# Inductive_measurement.net
KiCad netlist of a schematic drawn in Altium Designer
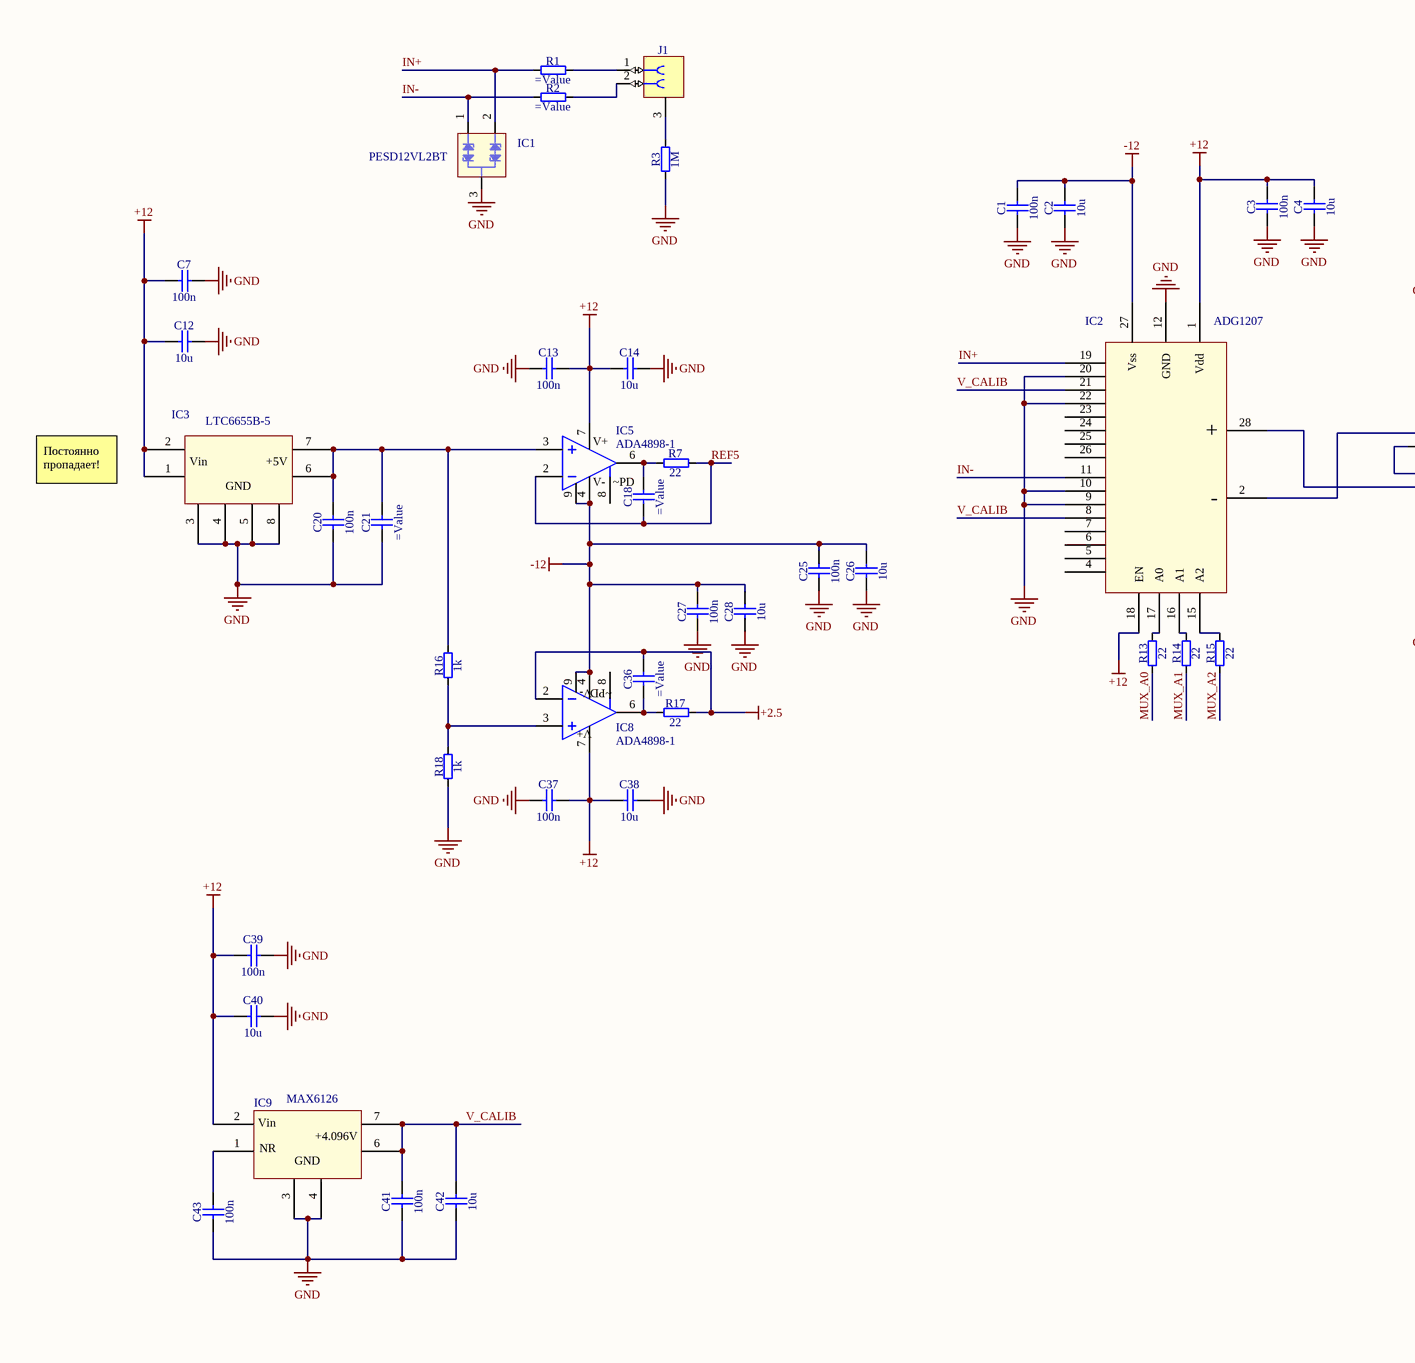
[diagram p0: Inductive_measurement.SchDoc, left]
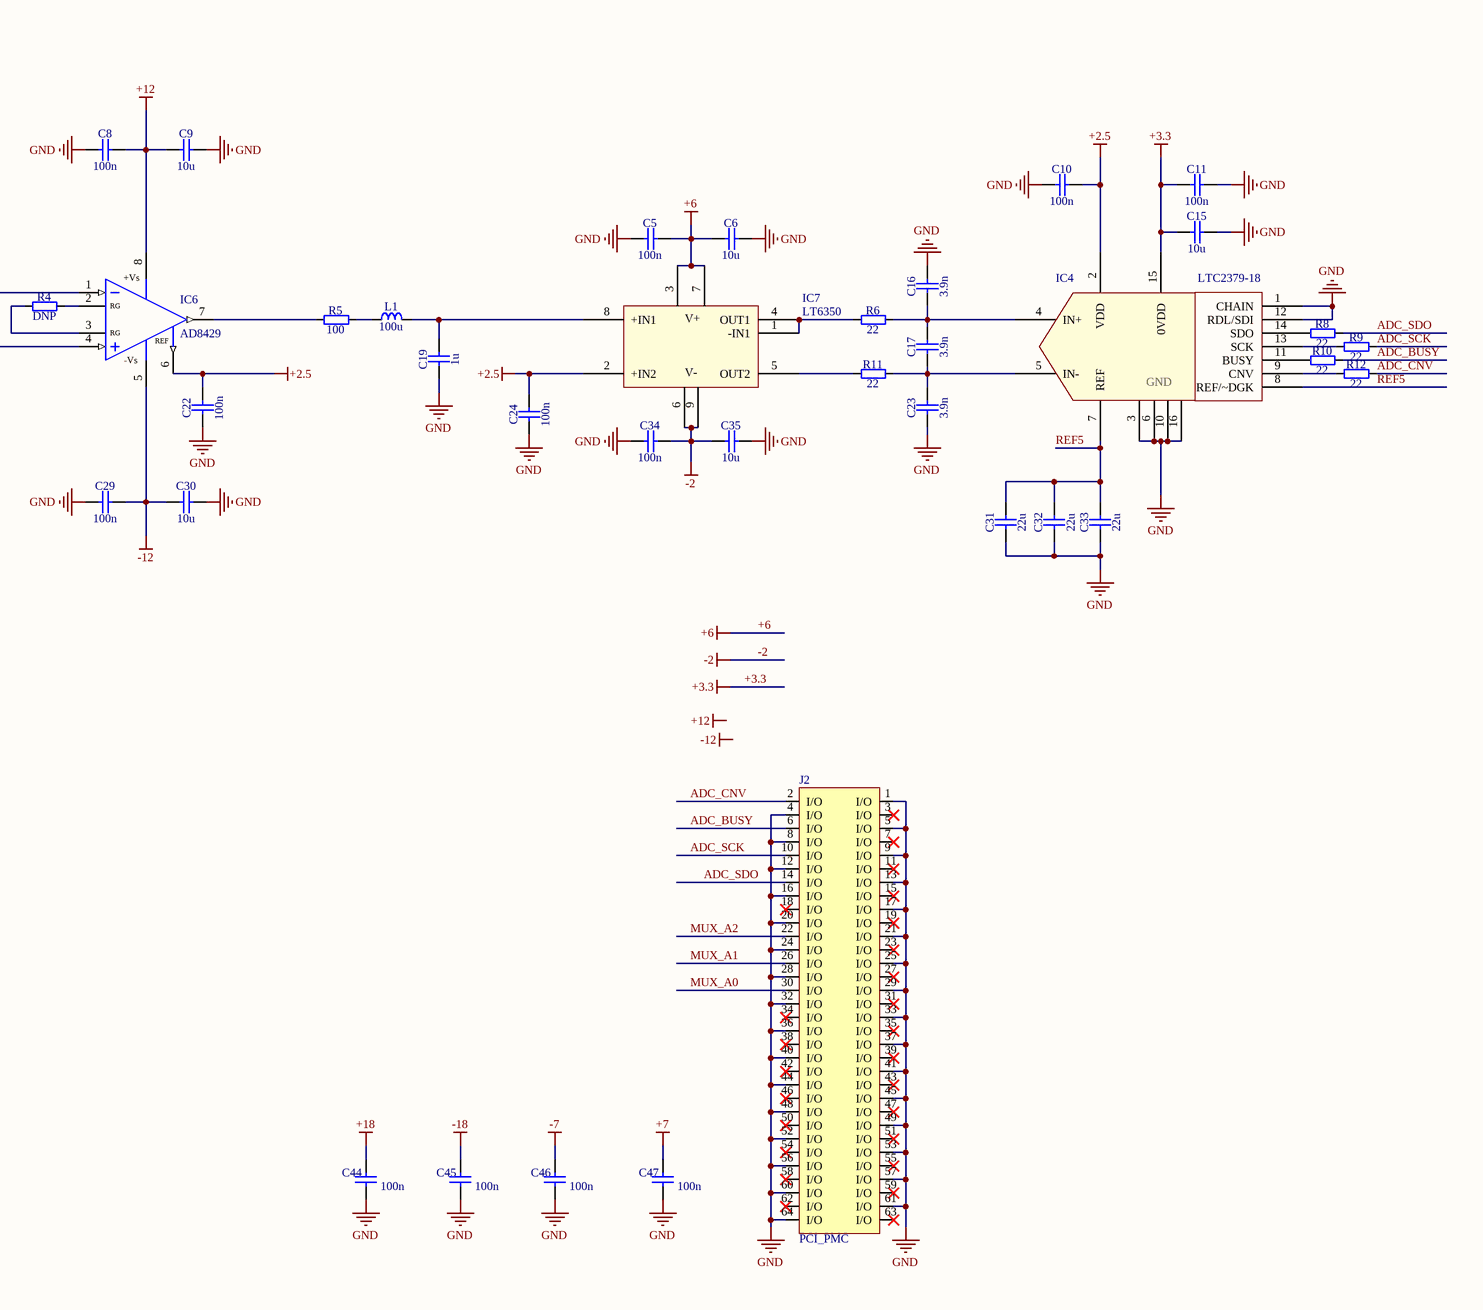
[diagram p1: Inductive_measurement.SchDoc, right]

(export (version "E")
  (design (tool "Eeschema 10.0.6"))
  (components
    (comp (ref "C1") (value "100n") (footprint "0603") (libsource (lib "intS") (part "Capacitor")))
    (comp (ref "C2") (value "10u") (footprint "0603") (libsource (lib "intS") (part "Capacitor")))
    (comp (ref "C3") (value "100n") (footprint "0603") (libsource (lib "intS") (part "Capacitor")))
    (comp (ref "C4") (value "10u") (footprint "0603") (libsource (lib "intS") (part "Capacitor")))
    (comp (ref "C5") (value "100n") (footprint "0603") (libsource (lib "intS") (part "Capacitor")))
    (comp (ref "C6") (value "10u") (footprint "0603") (libsource (lib "intS") (part "Capacitor")))
    (comp (ref "C7") (value "100n") (footprint "0603") (libsource (lib "intS") (part "Capacitor")))
    (comp (ref "C8") (value "100n") (footprint "0603") (libsource (lib "intS") (part "Capacitor")))
    (comp (ref "C9") (value "10u") (footprint "0603") (libsource (lib "intS") (part "Capacitor")))
    (comp (ref "C10") (value "100n") (footprint "0603") (libsource (lib "intS") (part "Capacitor")))
    (comp (ref "C11") (value "100n") (footprint "0603") (libsource (lib "intS") (part "Capacitor")))
    (comp (ref "C12") (value "10u") (footprint "0603") (libsource (lib "intS") (part "Capacitor")))
    (comp (ref "C13") (value "100n") (footprint "0603") (libsource (lib "intS") (part "Capacitor")))
    (comp (ref "C14") (value "10u") (footprint "0603") (libsource (lib "intS") (part "Capacitor")))
    (comp (ref "C15") (value "10u") (footprint "0603") (libsource (lib "intS") (part "Capacitor")))
    (comp (ref "C16") (value "3.9n") (footprint "0805") (libsource (lib "intS") (part "Capacitor")))
    (comp (ref "C17") (value "3.9n") (footprint "0805") (libsource (lib "intS") (part "Capacitor")))
    (comp (ref "C18") (value "~") (footprint "0603") (libsource (lib "intS") (part "Capacitor")))
    (comp (ref "C19")
      (value "1u")
      (footprint "CAPR500-450X730X950")
      (libsource (lib "intS") (part "Capacitor 4.5mm x 7.3mm"))
    )
    (comp (ref "C20") (value "100n") (footprint "0603") (libsource (lib "intS") (part "Capacitor")))
    (comp (ref "C21") (value "~") (footprint "0603") (libsource (lib "intS") (part "Capacitor")))
    (comp (ref "C22") (value "100n") (footprint "0603") (libsource (lib "intS") (part "Capacitor")))
    (comp (ref "C23") (value "3.9n") (footprint "0805") (libsource (lib "intS") (part "Capacitor")))
    (comp (ref "C24") (value "100n") (footprint "0603") (libsource (lib "intS") (part "Capacitor")))
    (comp (ref "C25") (value "100n") (footprint "0603") (libsource (lib "intS") (part "Capacitor")))
    (comp (ref "C26") (value "10u") (footprint "0603") (libsource (lib "intS") (part "Capacitor")))
    (comp (ref "C27") (value "100n") (footprint "0603") (libsource (lib "intS") (part "Capacitor")))
    (comp (ref "C28") (value "10u") (footprint "0603") (libsource (lib "intS") (part "Capacitor")))
    (comp (ref "C29") (value "100n") (footprint "0603") (libsource (lib "intS") (part "Capacitor")))
    (comp (ref "C30") (value "10u") (footprint "0603") (libsource (lib "intS") (part "Capacitor")))
    (comp (ref "C31") (value "22u") (footprint "0603") (libsource (lib "intS") (part "Capacitor")))
    (comp (ref "C32") (value "22u") (footprint "0603") (libsource (lib "intS") (part "Capacitor")))
    (comp (ref "C33") (value "22u") (footprint "0603") (libsource (lib "intS") (part "Capacitor")))
    (comp (ref "C34") (value "100n") (footprint "0603") (libsource (lib "intS") (part "Capacitor")))
    (comp (ref "C35") (value "10u") (footprint "0603") (libsource (lib "intS") (part "Capacitor")))
    (comp (ref "C36") (value "~") (footprint "0603") (libsource (lib "intS") (part "Capacitor")))
    (comp (ref "C37") (value "100n") (footprint "0603") (libsource (lib "intS") (part "Capacitor")))
    (comp (ref "C38") (value "10u") (footprint "0603") (libsource (lib "intS") (part "Capacitor")))
    (comp (ref "C39") (value "100n") (footprint "0603") (libsource (lib "intS") (part "Capacitor")))
    (comp (ref "C40") (value "10u") (footprint "0603") (libsource (lib "intS") (part "Capacitor")))
    (comp (ref "C41") (value "100n") (footprint "0603") (libsource (lib "intS") (part "Capacitor")))
    (comp (ref "C42") (value "10u") (footprint "0603") (libsource (lib "intS") (part "Capacitor")))
    (comp (ref "C43") (value "100n") (footprint "0603") (libsource (lib "intS") (part "Capacitor")))
    (comp (ref "C44") (value "100n") (footprint "0603") (libsource (lib "intS") (part "Capacitor")))
    (comp (ref "C45") (value "100n") (footprint "0603") (libsource (lib "intS") (part "Capacitor")))
    (comp (ref "C46") (value "100n") (footprint "0603") (libsource (lib "intS") (part "Capacitor")))
    (comp (ref "C47") (value "100n") (footprint "0603") (libsource (lib "intS") (part "Capacitor")))
    (comp (ref "IC1")
      (value "PESD12VL2BT")
      (footprint "SOT95P280X115-3N")
      (libsource (lib "intS") (part "PESD12VL2BT"))
    )
    (comp (ref "IC2")
      (value "ADG1207")
      (footprint "SOP65P640X120-28N")
      (description "8-channel multiplexer")
      (libsource (lib "intS") (part "ADG1207"))
    )
    (comp (ref "IC3")
      (value "LTC6655B-5")
      (footprint "SOP65P488X110-8N")
      (description "Reference, 5 V")
      (libsource (lib "intS") (part "LTC6655B-5"))
    )
    (comp (ref "IC4")
      (value "LTC2379-18")
      (footprint "SOP50P490X110-16N")
      (description "ADC")
      (libsource (lib "intS") (part "LTC2379-18"))
    )
    (comp (ref "IC5")
      (value "ADA4898-1")
      (footprint "SOIC127P600X175-9N-S229")
      (description "Op amp")
      (libsource (lib "intS") (part "ADA4898-1"))
    )
    (comp (ref "IC6")
      (value "AD8429")
      (footprint "SOIC127P600X175-8N")
      (description "1 nV/sqrt Hz Low Noise Instrumentation Amplifier")
      (libsource (lib "intS") (part "AD8429"))
    )
    (comp (ref "IC7")
      (value "LT6350")
      (footprint "SON50P300X300X80-9N-R175X248")
      (description "ADC driver")
      (libsource (lib "intS") (part "LT6350"))
    )
    (comp (ref "IC8")
      (value "ADA4898-1")
      (footprint "SOIC127P600X175-9N-S229")
      (description "Op amp")
      (libsource (lib "intS") (part "ADA4898-1"))
    )
    (comp (ref "IC9")
      (value "MAX6126")
      (footprint "SOIC127P600X175-8N")
      (description "Reference, 4.096 V")
      (libsource (lib "intS") (part "MAX6126AASA41"))
    )
    (comp (ref "J1")
      (value "~")
      (footprint "LEMO_EPG.0B.302.HLN")
      (description "Connector 2 Female")
      (libsource (lib "intS") (part "Connector 2 Female"))
    )
    (comp (ref "J2")
      (value "PCI_PMC")
      (footprint "TYCO_120527-1")
      (description "PCI Mezzanine Connector; IEEE 1386 Mezzanine board")
      (libsource (lib "intS") (part "PCI_PMC"))
    )
    (comp (ref "L1")
      (value "100u")
      (footprint "INDAD1524-920X400")
      (description "Inductor")
      (libsource (lib "intS") (part "Inductor"))
    )
    (comp (ref "R1") (value "~") (footprint "0603") (libsource (lib "intS") (part "Resistor")))
    (comp (ref "R2") (value "~") (footprint "0603") (libsource (lib "intS") (part "Resistor")))
    (comp (ref "R3") (value "1M") (footprint "0603") (libsource (lib "intS") (part "Resistor")))
    (comp (ref "R4") (value "DNP") (footprint "0805") (libsource (lib "intS") (part "Resistor")))
    (comp (ref "R5") (value "100") (footprint "0805") (libsource (lib "intS") (part "Resistor")))
    (comp (ref "R6") (value "22") (footprint "0805") (libsource (lib "intS") (part "Resistor")))
    (comp (ref "R7") (value "22") (footprint "0603") (libsource (lib "intS") (part "Resistor")))
    (comp (ref "R8") (value "22") (footprint "0603") (libsource (lib "intS") (part "Resistor")))
    (comp (ref "R9") (value "22") (footprint "0603") (libsource (lib "intS") (part "Resistor")))
    (comp (ref "R10") (value "22") (footprint "0603") (libsource (lib "intS") (part "Resistor")))
    (comp (ref "R11") (value "22") (footprint "0805") (libsource (lib "intS") (part "Resistor")))
    (comp (ref "R12") (value "22") (footprint "0603") (libsource (lib "intS") (part "Resistor")))
    (comp (ref "R13") (value "22") (footprint "0603") (libsource (lib "intS") (part "Resistor")))
    (comp (ref "R14") (value "22") (footprint "0603") (libsource (lib "intS") (part "Resistor")))
    (comp (ref "R15") (value "22") (footprint "0603") (libsource (lib "intS") (part "Resistor")))
    (comp (ref "R16") (value "1k") (footprint "0805") (libsource (lib "intS") (part "Resistor")))
    (comp (ref "R17") (value "22") (footprint "0603") (libsource (lib "intS") (part "Resistor")))
    (comp (ref "R18") (value "1k") (footprint "0805") (libsource (lib "intS") (part "Resistor")))
  )
  (nets
    (net (code "1") (name "+2.5") (class "Default")
      (node (ref "C10") (pin "2") (pinfunction "2_2") (pintype "passive"))
      (node (ref "C22") (pin "2") (pinfunction "2_2") (pintype "passive"))
      (node (ref "C24") (pin "2") (pinfunction "2_2") (pintype "passive"))
      (node (ref "C36") (pin "2") (pinfunction "2_2") (pintype "passive"))
      (node (ref "IC4") (pin "2") (pinfunction "VDD_2") (pintype "passive"))
      (node (ref "IC6") (pin "6") (pinfunction "REF_6") (pintype "output"))
      (node (ref "IC7") (pin "2") (pinfunction "+IN2_2") (pintype "passive"))
      (node (ref "IC8") (pin "2") (pinfunction "IN-_2") (pintype "passive"))
      (node (ref "R17") (pin "2") (pinfunction "2_2") (pintype "passive"))
    )
    (net (code "2") (name "+3.3") (class "Default")
      (node (ref "C11") (pin "1") (pinfunction "1_1") (pintype "passive"))
      (node (ref "C15") (pin "1") (pinfunction "1_1") (pintype "passive"))
      (node (ref "IC4") (pin "15") (pinfunction "0VDD_15") (pintype "passive"))
    )
    (net (code "3") (name "+6") (class "Default")
      (node (ref "C5") (pin "2") (pinfunction "2_2") (pintype "passive"))
      (node (ref "C6") (pin "1") (pinfunction "1_1") (pintype "passive"))
      (node (ref "IC7") (pin "3") (pinfunction "V+_3") (pintype "passive"))
      (node (ref "IC7") (pin "7") (pintype "passive"))
    )
    (net (code "4") (name "+7") (class "Default")
      (node (ref "C47") (pin "2") (pinfunction "2_2") (pintype "passive"))
    )
    (net (code "5") (name "+12") (class "Default")
      (node (ref "C12") (pin "1") (pinfunction "1_1") (pintype "passive"))
      (node (ref "C13") (pin "2") (pinfunction "2_2") (pintype "passive"))
      (node (ref "C14") (pin "1") (pinfunction "1_1") (pintype "passive"))
      (node (ref "C3") (pin "2") (pinfunction "2_2") (pintype "passive"))
      (node (ref "C37") (pin "1") (pinfunction "1_1") (pintype "passive"))
      (node (ref "C38") (pin "2") (pinfunction "2_2") (pintype "passive"))
      (node (ref "C39") (pin "1") (pinfunction "1_1") (pintype "passive"))
      (node (ref "C4") (pin "2") (pinfunction "2_2") (pintype "passive"))
      (node (ref "C40") (pin "1") (pinfunction "1_1") (pintype "passive"))
      (node (ref "C7") (pin "1") (pinfunction "1_1") (pintype "passive"))
      (node (ref "C8") (pin "2") (pinfunction "2_2") (pintype "passive"))
      (node (ref "C9") (pin "1") (pinfunction "1_1") (pintype "passive"))
      (node (ref "IC2") (pin "1") (pinfunction "Vdd_1") (pintype "passive"))
      (node (ref "IC2") (pin "18") (pinfunction "EN_18") (pintype "passive"))
      (node (ref "IC3") (pin "1") (pintype "passive"))
      (node (ref "IC3") (pin "2") (pintype "passive"))
      (node (ref "IC5") (pin "7") (pinfunction "V+_7") (pintype "passive"))
      (node (ref "IC6") (pin "8") (pinfunction "+Vs_8") (pintype "power_in"))
      (node (ref "IC8") (pin "7") (pinfunction "V+_7") (pintype "passive"))
      (node (ref "IC9") (pin "2") (pintype "passive"))
    )
    (net (code "6") (name "+18") (class "Default")
      (node (ref "C44") (pin "2") (pinfunction "2_2") (pintype "passive"))
    )
    (net (code "7") (name "-2") (class "Default")
      (node (ref "C34") (pin "2") (pinfunction "2_2") (pintype "passive"))
      (node (ref "C35") (pin "1") (pinfunction "1_1") (pintype "passive"))
      (node (ref "IC7") (pin "6") (pinfunction "V-_6") (pintype "passive"))
      (node (ref "IC7") (pin "9") (pinfunction "V-_9") (pintype "passive"))
    )
    (net (code "8") (name "-7") (class "Default")
      (node (ref "C46") (pin "2") (pinfunction "2_2") (pintype "passive"))
    )
    (net (code "9") (name "-12") (class "Default")
      (node (ref "C1") (pin "2") (pinfunction "2_2") (pintype "passive"))
      (node (ref "C2") (pin "2") (pinfunction "2_2") (pintype "passive"))
      (node (ref "C25") (pin "2") (pinfunction "2_2") (pintype "passive"))
      (node (ref "C26") (pin "2") (pinfunction "2_2") (pintype "passive"))
      (node (ref "C27") (pin "2") (pinfunction "2_2") (pintype "passive"))
      (node (ref "C28") (pin "2") (pinfunction "2_2") (pintype "passive"))
      (node (ref "C29") (pin "2") (pinfunction "2_2") (pintype "passive"))
      (node (ref "C30") (pin "1") (pinfunction "1_1") (pintype "passive"))
      (node (ref "IC2") (pin "27") (pinfunction "Vss_27") (pintype "passive"))
      (node (ref "IC5") (pin "4") (pinfunction "V-_4") (pintype "passive"))
      (node (ref "IC5") (pin "9") (pinfunction "EXPOSED_PAD_9") (pintype "passive"))
      (node (ref "IC6") (pin "5") (pinfunction "-Vs_5") (pintype "power_in"))
      (node (ref "IC8") (pin "4") (pinfunction "V-_4") (pintype "passive"))
      (node (ref "IC8") (pin "9") (pinfunction "EXPOSED_PAD_9") (pintype "passive"))
    )
    (net (code "10") (name "-18") (class "Default")
      (node (ref "C45") (pin "2") (pinfunction "2_2") (pintype "passive"))
    )
    (net (code "11") (name "/ADC_BUSY") (class "Default")
      (node (ref "J2") (pin "6") (pinfunction "I/O_6") (pintype "bidirectional"))
      (node (ref "R10") (pin "2") (pinfunction "2_2") (pintype "passive"))
    )
    (net (code "12") (name "/ADC_CNV") (class "Default")
      (node (ref "J2") (pin "2") (pinfunction "I/O_2") (pintype "bidirectional"))
      (node (ref "R12") (pin "2") (pinfunction "2_2") (pintype "passive"))
    )
    (net (code "13") (name "/ADC_SCK") (class "Default")
      (node (ref "J2") (pin "10") (pinfunction "I/O_10") (pintype "bidirectional"))
      (node (ref "R9") (pin "2") (pinfunction "2_2") (pintype "passive"))
    )
    (net (code "14") (name "/ADC_SDO") (class "Default")
      (node (ref "J2") (pin "14") (pinfunction "I/O_14") (pintype "bidirectional"))
      (node (ref "R8") (pin "2") (pinfunction "2_2") (pintype "passive"))
    )
    (net (code "15") (name "/IN+") (class "Default")
      (node (ref "IC1") (pin "2") (pinfunction "C2_2") (pintype "passive"))
      (node (ref "IC2") (pin "19") (pintype "passive"))
      (node (ref "R1") (pin "1") (pinfunction "1_1") (pintype "passive"))
    )
    (net (code "16") (name "/IN-") (class "Default")
      (node (ref "IC1") (pin "1") (pinfunction "C1_1") (pintype "passive"))
      (node (ref "IC2") (pin "11") (pintype "passive"))
      (node (ref "R2") (pin "1") (pinfunction "1_1") (pintype "passive"))
    )
    (net (code "17") (name "/MUX_A0") (class "Default")
      (node (ref "J2") (pin "30") (pinfunction "I/O_30") (pintype "bidirectional"))
      (node (ref "R13") (pin "1") (pinfunction "1_1") (pintype "passive"))
    )
    (net (code "18") (name "/MUX_A1") (class "Default")
      (node (ref "J2") (pin "26") (pinfunction "I/O_26") (pintype "bidirectional"))
      (node (ref "R14") (pin "1") (pinfunction "1_1") (pintype "passive"))
    )
    (net (code "19") (name "/MUX_A2") (class "Default")
      (node (ref "J2") (pin "22") (pinfunction "I/O_22") (pintype "bidirectional"))
      (node (ref "R15") (pin "1") (pinfunction "1_1") (pintype "passive"))
    )
    (net (code "20") (name "/REF5") (class "Default")
      (node (ref "C18") (pin "1") (pinfunction "1_1") (pintype "passive"))
      (node (ref "C31") (pin "2") (pinfunction "2_2") (pintype "passive"))
      (node (ref "C32") (pin "2") (pinfunction "2_2") (pintype "passive"))
      (node (ref "C33") (pin "2") (pinfunction "2_2") (pintype "passive"))
      (node (ref "IC4") (pin "7") (pinfunction "REF_7") (pintype "passive"))
      (node (ref "IC4") (pin "8") (pinfunction "REF/~DGK_8") (pintype "passive"))
      (node (ref "IC5") (pin "2") (pinfunction "IN-_2") (pintype "passive"))
      (node (ref "R7") (pin "2") (pinfunction "2_2") (pintype "passive"))
    )
    (net (code "21") (name "/V_CALIB") (class "Default")
      (node (ref "C41") (pin "2") (pinfunction "2_2") (pintype "passive"))
      (node (ref "C42") (pin "2") (pinfunction "2_2") (pintype "passive"))
      (node (ref "IC2") (pin "21") (pintype "passive"))
      (node (ref "IC2") (pin "8") (pintype "passive"))
      (node (ref "IC9") (pin "6") (pintype "passive"))
      (node (ref "IC9") (pin "7") (pintype "passive"))
    )
    (net (code "22") (name "GND") (class "Default")
      (node (ref "C1") (pin "1") (pinfunction "1_1") (pintype "passive"))
      (node (ref "C10") (pin "1") (pinfunction "1_1") (pintype "passive"))
      (node (ref "C11") (pin "2") (pinfunction "2_2") (pintype "passive"))
      (node (ref "C12") (pin "2") (pinfunction "2_2") (pintype "passive"))
      (node (ref "C13") (pin "1") (pinfunction "1_1") (pintype "passive"))
      (node (ref "C14") (pin "2") (pinfunction "2_2") (pintype "passive"))
      (node (ref "C15") (pin "2") (pinfunction "2_2") (pintype "passive"))
      (node (ref "C16") (pin "2") (pinfunction "2_2") (pintype "passive"))
      (node (ref "C19") (pin "1") (pinfunction "1_1") (pintype "passive"))
      (node (ref "C2") (pin "1") (pinfunction "1_1") (pintype "passive"))
      (node (ref "C20") (pin "1") (pinfunction "1_1") (pintype "passive"))
      (node (ref "C21") (pin "1") (pinfunction "1_1") (pintype "passive"))
      (node (ref "C22") (pin "1") (pinfunction "1_1") (pintype "passive"))
      (node (ref "C23") (pin "1") (pinfunction "1_1") (pintype "passive"))
      (node (ref "C24") (pin "1") (pinfunction "1_1") (pintype "passive"))
      (node (ref "C25") (pin "1") (pinfunction "1_1") (pintype "passive"))
      (node (ref "C26") (pin "1") (pinfunction "1_1") (pintype "passive"))
      (node (ref "C27") (pin "1") (pinfunction "1_1") (pintype "passive"))
      (node (ref "C28") (pin "1") (pinfunction "1_1") (pintype "passive"))
      (node (ref "C29") (pin "1") (pinfunction "1_1") (pintype "passive"))
      (node (ref "C3") (pin "1") (pinfunction "1_1") (pintype "passive"))
      (node (ref "C30") (pin "2") (pinfunction "2_2") (pintype "passive"))
      (node (ref "C31") (pin "1") (pinfunction "1_1") (pintype "passive"))
      (node (ref "C32") (pin "1") (pinfunction "1_1") (pintype "passive"))
      (node (ref "C33") (pin "1") (pinfunction "1_1") (pintype "passive"))
      (node (ref "C34") (pin "1") (pinfunction "1_1") (pintype "passive"))
      (node (ref "C35") (pin "2") (pinfunction "2_2") (pintype "passive"))
      (node (ref "C37") (pin "2") (pinfunction "2_2") (pintype "passive"))
      (node (ref "C38") (pin "1") (pinfunction "1_1") (pintype "passive"))
      (node (ref "C39") (pin "2") (pinfunction "2_2") (pintype "passive"))
      (node (ref "C4") (pin "1") (pinfunction "1_1") (pintype "passive"))
      (node (ref "C40") (pin "2") (pinfunction "2_2") (pintype "passive"))
      (node (ref "C41") (pin "1") (pinfunction "1_1") (pintype "passive"))
      (node (ref "C42") (pin "1") (pinfunction "1_1") (pintype "passive"))
      (node (ref "C43") (pin "1") (pinfunction "1_1") (pintype "passive"))
      (node (ref "C44") (pin "1") (pinfunction "1_1") (pintype "passive"))
      (node (ref "C45") (pin "1") (pinfunction "1_1") (pintype "passive"))
      (node (ref "C46") (pin "1") (pinfunction "1_1") (pintype "passive"))
      (node (ref "C47") (pin "1") (pinfunction "1_1") (pintype "passive"))
      (node (ref "C5") (pin "1") (pinfunction "1_1") (pintype "passive"))
      (node (ref "C6") (pin "2") (pinfunction "2_2") (pintype "passive"))
      (node (ref "C7") (pin "2") (pinfunction "2_2") (pintype "passive"))
      (node (ref "C8") (pin "1") (pinfunction "1_1") (pintype "passive"))
      (node (ref "C9") (pin "2") (pinfunction "2_2") (pintype "passive"))
      (node (ref "IC1") (pin "3") (pinfunction "double_cathode_3") (pintype "passive"))
      (node (ref "IC2") (pin "10") (pintype "passive"))
      (node (ref "IC2") (pin "12") (pinfunction "GND_12") (pintype "passive"))
      (node (ref "IC2") (pin "20") (pintype "passive"))
      (node (ref "IC2") (pin "22") (pintype "passive"))
      (node (ref "IC2") (pin "9") (pintype "passive"))
      (node (ref "IC3") (pin "3") (pintype "passive"))
      (node (ref "IC3") (pin "4") (pintype "passive"))
      (node (ref "IC3") (pin "5") (pintype "passive"))
      (node (ref "IC3") (pin "8") (pintype "passive"))
      (node (ref "IC4") (pin "1") (pinfunction "CHAIN_1") (pintype "passive"))
      (node (ref "IC4") (pin "10") (pintype "passive"))
      (node (ref "IC4") (pin "12") (pinfunction "RDL/SDI_12") (pintype "passive"))
      (node (ref "IC4") (pin "16") (pintype "passive"))
      (node (ref "IC4") (pin "3") (pintype "passive"))
      (node (ref "IC4") (pin "6") (pintype "passive"))
      (node (ref "IC9") (pin "3") (pintype "passive"))
      (node (ref "IC9") (pin "4") (pintype "passive"))
      (node (ref "J2") (pin "1") (pinfunction "I/O_1") (pintype "bidirectional"))
      (node (ref "J2") (pin "12") (pinfunction "I/O_12") (pintype "bidirectional"))
      (node (ref "J2") (pin "13") (pinfunction "I/O_13") (pintype "bidirectional"))
      (node (ref "J2") (pin "16") (pinfunction "I/O_16") (pintype "bidirectional"))
      (node (ref "J2") (pin "17") (pinfunction "I/O_17") (pintype "bidirectional"))
      (node (ref "J2") (pin "20") (pinfunction "I/O_20") (pintype "bidirectional"))
      (node (ref "J2") (pin "21") (pinfunction "I/O_21") (pintype "bidirectional"))
      (node (ref "J2") (pin "24") (pinfunction "I/O_24") (pintype "bidirectional"))
      (node (ref "J2") (pin "25") (pinfunction "I/O_25") (pintype "bidirectional"))
      (node (ref "J2") (pin "28") (pinfunction "I/O_28") (pintype "bidirectional"))
      (node (ref "J2") (pin "29") (pinfunction "I/O_29") (pintype "bidirectional"))
      (node (ref "J2") (pin "32") (pinfunction "I/O_32") (pintype "bidirectional"))
      (node (ref "J2") (pin "33") (pinfunction "I/O_33") (pintype "bidirectional"))
      (node (ref "J2") (pin "36") (pinfunction "I/O_36") (pintype "bidirectional"))
      (node (ref "J2") (pin "37") (pinfunction "I/O_37") (pintype "bidirectional"))
      (node (ref "J2") (pin "4") (pinfunction "I/O_4") (pintype "bidirectional"))
      (node (ref "J2") (pin "40") (pinfunction "I/O_40") (pintype "bidirectional"))
      (node (ref "J2") (pin "41") (pinfunction "I/O_41") (pintype "bidirectional"))
      (node (ref "J2") (pin "44") (pinfunction "I/O_44") (pintype "bidirectional"))
      (node (ref "J2") (pin "45") (pinfunction "I/O_45") (pintype "bidirectional"))
      (node (ref "J2") (pin "48") (pinfunction "I/O_48") (pintype "bidirectional"))
      (node (ref "J2") (pin "49") (pinfunction "I/O_49") (pintype "bidirectional"))
      (node (ref "J2") (pin "5") (pinfunction "I/O_5") (pintype "bidirectional"))
      (node (ref "J2") (pin "52") (pinfunction "I/O_52") (pintype "bidirectional"))
      (node (ref "J2") (pin "53") (pinfunction "I/O_53") (pintype "bidirectional"))
      (node (ref "J2") (pin "56") (pinfunction "I/O_56") (pintype "bidirectional"))
      (node (ref "J2") (pin "57") (pinfunction "I/O_57") (pintype "bidirectional"))
      (node (ref "J2") (pin "60") (pinfunction "I/O_60") (pintype "bidirectional"))
      (node (ref "J2") (pin "61") (pinfunction "I/O_61") (pintype "bidirectional"))
      (node (ref "J2") (pin "64") (pinfunction "I/O_64") (pintype "bidirectional"))
      (node (ref "J2") (pin "8") (pinfunction "I/O_8") (pintype "bidirectional"))
      (node (ref "J2") (pin "9") (pinfunction "I/O_9") (pintype "bidirectional"))
      (node (ref "R18") (pin "1") (pinfunction "1_1") (pintype "passive"))
      (node (ref "R3") (pin "1") (pinfunction "1_1") (pintype "passive"))
    )
    (net (code "23") (name "Net-(C43-Pad2)") (class "Default")
      (node (ref "C43") (pin "2") (pinfunction "2_2") (pintype "passive"))
      (node (ref "IC9") (pin "1") (pintype "passive"))
    )
    (net (code "24") (name "Net-(IC2-+)") (class "Default")
      (node (ref "IC2") (pin "28") (pinfunction "+_28") (pintype "passive"))
      (node (ref "IC6") (pin "4") (pinfunction "+IN_4") (pintype "input"))
    )
    (net (code "25") (name "Net-(IC2--)") (class "Default")
      (node (ref "IC2") (pin "2") (pinfunction "-_2") (pintype "passive"))
      (node (ref "IC6") (pin "1") (pinfunction "-IN_1") (pintype "input"))
    )
    (net (code "26") (name "Net-(IC2-A0)") (class "Default")
      (node (ref "IC2") (pin "17") (pinfunction "A0_17") (pintype "passive"))
      (node (ref "R13") (pin "2") (pinfunction "2_2") (pintype "passive"))
    )
    (net (code "27") (name "Net-(IC2-A1)") (class "Default")
      (node (ref "IC2") (pin "16") (pinfunction "A1_16") (pintype "passive"))
      (node (ref "R14") (pin "2") (pinfunction "2_2") (pintype "passive"))
    )
    (net (code "28") (name "Net-(IC2-A2)") (class "Default")
      (node (ref "IC2") (pin "15") (pinfunction "A2_15") (pintype "passive"))
      (node (ref "R15") (pin "2") (pinfunction "2_2") (pintype "passive"))
    )
    (net (code "29") (name "Net-(IC4-BUSY)") (class "Default")
      (node (ref "IC4") (pin "11") (pinfunction "BUSY_11") (pintype "passive"))
      (node (ref "R10") (pin "1") (pinfunction "1_1") (pintype "passive"))
    )
    (net (code "30") (name "Net-(IC4-CNV)") (class "Default")
      (node (ref "IC4") (pin "9") (pinfunction "CNV_9") (pintype "passive"))
      (node (ref "R12") (pin "1") (pinfunction "1_1") (pintype "passive"))
    )
    (net (code "31") (name "Net-(IC4-IN+)") (class "Default")
      (node (ref "C16") (pin "1") (pinfunction "1_1") (pintype "passive"))
      (node (ref "C17") (pin "2") (pinfunction "2_2") (pintype "passive"))
      (node (ref "IC4") (pin "4") (pinfunction "IN+_4") (pintype "passive"))
      (node (ref "R6") (pin "2") (pinfunction "2_2") (pintype "passive"))
    )
    (net (code "32") (name "Net-(IC4-IN-)") (class "Default")
      (node (ref "C17") (pin "1") (pinfunction "1_1") (pintype "passive"))
      (node (ref "C23") (pin "2") (pinfunction "2_2") (pintype "passive"))
      (node (ref "IC4") (pin "5") (pinfunction "IN-_5") (pintype "passive"))
      (node (ref "R11") (pin "2") (pinfunction "2_2") (pintype "passive"))
    )
    (net (code "33") (name "Net-(IC4-SCK)") (class "Default")
      (node (ref "IC4") (pin "13") (pinfunction "SCK_13") (pintype "passive"))
      (node (ref "R9") (pin "1") (pinfunction "1_1") (pintype "passive"))
    )
    (net (code "34") (name "Net-(IC4-SDO)") (class "Default")
      (node (ref "IC4") (pin "14") (pinfunction "SDO_14") (pintype "passive"))
      (node (ref "R8") (pin "1") (pinfunction "1_1") (pintype "passive"))
    )
    (net (code "35") (name "Net-(IC5-IN+)") (class "Default")
      (node (ref "C20") (pin "2") (pinfunction "2_2") (pintype "passive"))
      (node (ref "C21") (pin "2") (pinfunction "2_2") (pintype "passive"))
      (node (ref "IC3") (pin "6") (pintype "passive"))
      (node (ref "IC3") (pin "7") (pintype "passive"))
      (node (ref "IC5") (pin "3") (pinfunction "IN+_3") (pintype "passive"))
      (node (ref "R16") (pin "2") (pinfunction "2_2") (pintype "passive"))
    )
    (net (code "36") (name "Net-(IC5-OUT)") (class "Default")
      (node (ref "C18") (pin "2") (pinfunction "2_2") (pintype "passive"))
      (node (ref "IC5") (pin "6") (pinfunction "OUT_6") (pintype "passive"))
      (node (ref "R7") (pin "1") (pinfunction "1_1") (pintype "passive"))
    )
    (net (code "37") (name "Net-(IC6-RG-Pad2)") (class "Default")
      (node (ref "IC6") (pin "2") (pinfunction "RG_2") (pintype "passive"))
      (node (ref "R4") (pin "2") (pinfunction "2_2") (pintype "passive"))
    )
    (net (code "38") (name "Net-(IC6-RG-Pad3)") (class "Default")
      (node (ref "IC6") (pin "3") (pinfunction "RG_3") (pintype "passive"))
      (node (ref "R4") (pin "1") (pinfunction "1_1") (pintype "passive"))
    )
    (net (code "39") (name "Net-(IC6-Vout)") (class "Default")
      (node (ref "IC6") (pin "7") (pinfunction "Vout_7") (pintype "output"))
      (node (ref "R5") (pin "1") (pinfunction "1_1") (pintype "passive"))
    )
    (net (code "40") (name "Net-(IC7-+IN1)") (class "Default")
      (node (ref "C19") (pin "2") (pinfunction "2_2") (pintype "passive"))
      (node (ref "IC7") (pin "8") (pinfunction "+IN1_8") (pintype "passive"))
      (node (ref "L1") (pin "2") (pinfunction "2_2") (pintype "passive"))
    )
    (net (code "41") (name "Net-(IC7--IN1)") (class "Default")
      (node (ref "IC7") (pin "1") (pinfunction "-IN1_1") (pintype "passive"))
      (node (ref "IC7") (pin "4") (pinfunction "OUT1_4") (pintype "passive"))
      (node (ref "R6") (pin "1") (pinfunction "1_1") (pintype "passive"))
    )
    (net (code "42") (name "Net-(IC7-OUT2)") (class "Default")
      (node (ref "IC7") (pin "5") (pinfunction "OUT2_5") (pintype "passive"))
      (node (ref "R11") (pin "1") (pinfunction "1_1") (pintype "passive"))
    )
    (net (code "43") (name "Net-(IC8-IN+)") (class "Default")
      (node (ref "IC8") (pin "3") (pinfunction "IN+_3") (pintype "passive"))
      (node (ref "R16") (pin "1") (pinfunction "1_1") (pintype "passive"))
      (node (ref "R18") (pin "2") (pinfunction "2_2") (pintype "passive"))
    )
    (net (code "44") (name "Net-(IC8-OUT)") (class "Default")
      (node (ref "C36") (pin "1") (pinfunction "1_1") (pintype "passive"))
      (node (ref "IC8") (pin "6") (pinfunction "OUT_6") (pintype "passive"))
      (node (ref "R17") (pin "1") (pinfunction "1_1") (pintype "passive"))
    )
    (net (code "45") (name "Net-(J1-Pad1)") (class "Default")
      (node (ref "J1") (pin "1") (pinfunction "1_1") (pintype "bidirectional"))
      (node (ref "R1") (pin "2") (pinfunction "2_2") (pintype "passive"))
    )
    (net (code "46") (name "Net-(J1-Pad2)") (class "Default")
      (node (ref "J1") (pin "2") (pinfunction "2_2") (pintype "bidirectional"))
      (node (ref "R2") (pin "2") (pinfunction "2_2") (pintype "passive"))
    )
    (net (code "47") (name "Net-(J1-Pad3)") (class "Default")
      (node (ref "J1") (pin "3") (pinfunction "3_3") (pintype "passive"))
      (node (ref "R3") (pin "2") (pinfunction "2_2") (pintype "passive"))
    )
    (net (code "48") (name "Net-(L1-Pad1)") (class "Default")
      (node (ref "L1") (pin "1") (pinfunction "1_1") (pintype "passive"))
      (node (ref "R5") (pin "2") (pinfunction "2_2") (pintype "passive"))
    )
    (net (code "49") (name "unconnected-(IC2-Pad4)") (class "Default")
      (node (ref "IC2") (pin "4") (pintype "passive"))
    )
    (net (code "50") (name "unconnected-(IC2-Pad5)") (class "Default")
      (node (ref "IC2") (pin "5") (pintype "passive"))
    )
    (net (code "51") (name "unconnected-(IC2-Pad6)") (class "Default")
      (node (ref "IC2") (pin "6") (pintype "passive"))
    )
    (net (code "52") (name "unconnected-(IC2-Pad7)") (class "Default")
      (node (ref "IC2") (pin "7") (pintype "passive"))
    )
    (net (code "53") (name "unconnected-(IC2-Pad23)") (class "Default")
      (node (ref "IC2") (pin "23") (pintype "passive"))
    )
    (net (code "54") (name "unconnected-(IC2-Pad24)") (class "Default")
      (node (ref "IC2") (pin "24") (pintype "passive"))
    )
    (net (code "55") (name "unconnected-(IC2-Pad25)") (class "Default")
      (node (ref "IC2") (pin "25") (pintype "passive"))
    )
    (net (code "56") (name "unconnected-(IC2-Pad26)") (class "Default")
      (node (ref "IC2") (pin "26") (pintype "passive"))
    )
    (net (code "57") (name "unconnected-(IC5-~PD-Pad8)") (class "Default")
      (node (ref "IC5") (pin "8") (pinfunction "~PD_8") (pintype "passive"))
    )
    (net (code "58") (name "unconnected-(IC8-~PD-Pad8)") (class "Default")
      (node (ref "IC8") (pin "8") (pinfunction "~PD_8") (pintype "passive"))
    )
    (net (code "59") (name "unconnected-(J2-I{slash}O-Pad3)") (class "Default")
      (node (ref "J2") (pin "3") (pinfunction "I/O_3") (pintype "bidirectional+no_connect"))
    )
    (net (code "60") (name "unconnected-(J2-I{slash}O-Pad7)") (class "Default")
      (node (ref "J2") (pin "7") (pinfunction "I/O_7") (pintype "bidirectional+no_connect"))
    )
    (net (code "61") (name "unconnected-(J2-I{slash}O-Pad11)") (class "Default")
      (node (ref "J2") (pin "11") (pinfunction "I/O_11") (pintype "bidirectional+no_connect"))
    )
    (net (code "62") (name "unconnected-(J2-I{slash}O-Pad15)") (class "Default")
      (node (ref "J2") (pin "15") (pinfunction "I/O_15") (pintype "bidirectional+no_connect"))
    )
    (net (code "63") (name "unconnected-(J2-I{slash}O-Pad18)") (class "Default")
      (node (ref "J2") (pin "18") (pinfunction "I/O_18") (pintype "bidirectional+no_connect"))
    )
    (net (code "64") (name "unconnected-(J2-I{slash}O-Pad19)") (class "Default")
      (node (ref "J2") (pin "19") (pinfunction "I/O_19") (pintype "bidirectional+no_connect"))
    )
    (net (code "65") (name "unconnected-(J2-I{slash}O-Pad23)") (class "Default")
      (node (ref "J2") (pin "23") (pinfunction "I/O_23") (pintype "bidirectional+no_connect"))
    )
    (net (code "66") (name "unconnected-(J2-I{slash}O-Pad27)") (class "Default")
      (node (ref "J2") (pin "27") (pinfunction "I/O_27") (pintype "bidirectional+no_connect"))
    )
    (net (code "67") (name "unconnected-(J2-I{slash}O-Pad31)") (class "Default")
      (node (ref "J2") (pin "31") (pinfunction "I/O_31") (pintype "bidirectional+no_connect"))
    )
    (net (code "68") (name "unconnected-(J2-I{slash}O-Pad34)") (class "Default")
      (node (ref "J2") (pin "34") (pinfunction "I/O_34") (pintype "bidirectional+no_connect"))
    )
    (net (code "69") (name "unconnected-(J2-I{slash}O-Pad35)") (class "Default")
      (node (ref "J2") (pin "35") (pinfunction "I/O_35") (pintype "bidirectional+no_connect"))
    )
    (net (code "70") (name "unconnected-(J2-I{slash}O-Pad38)") (class "Default")
      (node (ref "J2") (pin "38") (pinfunction "I/O_38") (pintype "bidirectional+no_connect"))
    )
    (net (code "71") (name "unconnected-(J2-I{slash}O-Pad39)") (class "Default")
      (node (ref "J2") (pin "39") (pinfunction "I/O_39") (pintype "bidirectional+no_connect"))
    )
    (net (code "72") (name "unconnected-(J2-I{slash}O-Pad42)") (class "Default")
      (node (ref "J2") (pin "42") (pinfunction "I/O_42") (pintype "bidirectional+no_connect"))
    )
    (net (code "73") (name "unconnected-(J2-I{slash}O-Pad43)") (class "Default")
      (node (ref "J2") (pin "43") (pinfunction "I/O_43") (pintype "bidirectional+no_connect"))
    )
    (net (code "74") (name "unconnected-(J2-I{slash}O-Pad46)") (class "Default")
      (node (ref "J2") (pin "46") (pinfunction "I/O_46") (pintype "bidirectional+no_connect"))
    )
    (net (code "75") (name "unconnected-(J2-I{slash}O-Pad47)") (class "Default")
      (node (ref "J2") (pin "47") (pinfunction "I/O_47") (pintype "bidirectional+no_connect"))
    )
    (net (code "76") (name "unconnected-(J2-I{slash}O-Pad50)") (class "Default")
      (node (ref "J2") (pin "50") (pinfunction "I/O_50") (pintype "bidirectional+no_connect"))
    )
    (net (code "77") (name "unconnected-(J2-I{slash}O-Pad51)") (class "Default")
      (node (ref "J2") (pin "51") (pinfunction "I/O_51") (pintype "bidirectional+no_connect"))
    )
    (net (code "78") (name "unconnected-(J2-I{slash}O-Pad54)") (class "Default")
      (node (ref "J2") (pin "54") (pinfunction "I/O_54") (pintype "bidirectional+no_connect"))
    )
    (net (code "79") (name "unconnected-(J2-I{slash}O-Pad55)") (class "Default")
      (node (ref "J2") (pin "55") (pinfunction "I/O_55") (pintype "bidirectional+no_connect"))
    )
    (net (code "80") (name "unconnected-(J2-I{slash}O-Pad58)") (class "Default")
      (node (ref "J2") (pin "58") (pinfunction "I/O_58") (pintype "bidirectional+no_connect"))
    )
    (net (code "81") (name "unconnected-(J2-I{slash}O-Pad59)") (class "Default")
      (node (ref "J2") (pin "59") (pinfunction "I/O_59") (pintype "bidirectional+no_connect"))
    )
    (net (code "82") (name "unconnected-(J2-I{slash}O-Pad62)") (class "Default")
      (node (ref "J2") (pin "62") (pinfunction "I/O_62") (pintype "bidirectional+no_connect"))
    )
    (net (code "83") (name "unconnected-(J2-I{slash}O-Pad63)") (class "Default")
      (node (ref "J2") (pin "63") (pinfunction "I/O_63") (pintype "bidirectional+no_connect"))
    )
  )
)
